# CON_SPDIF_OUT.net
KiCad netlist of a schematic drawn in Altium Designer
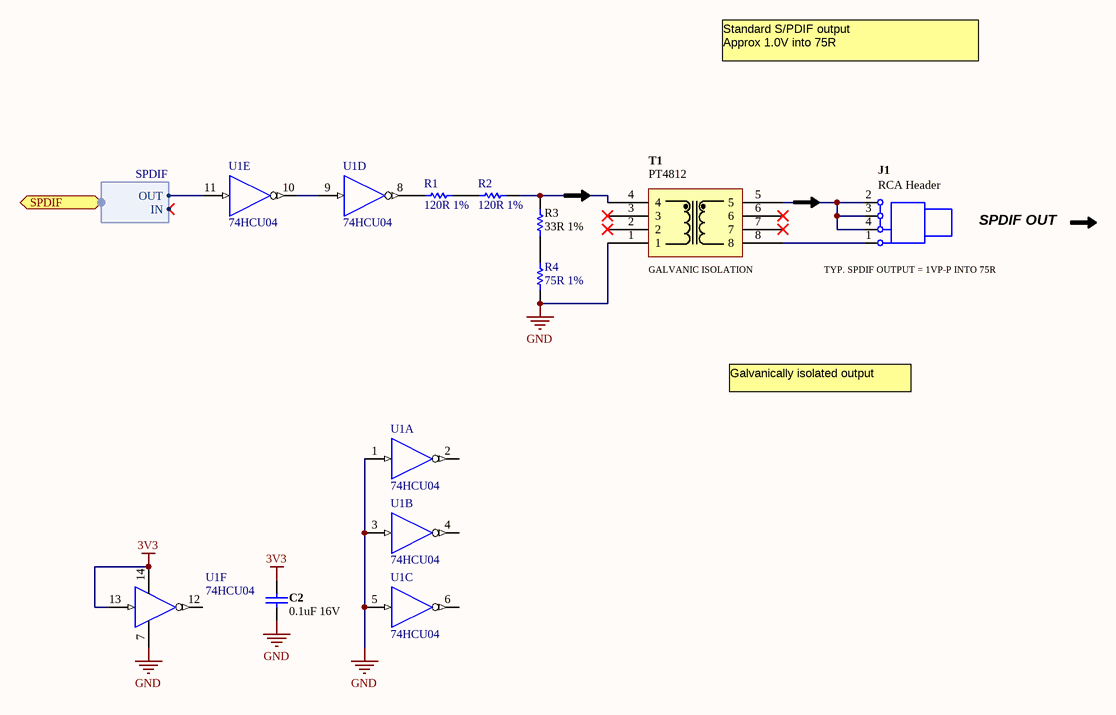
[diagram p0: CON_SPDIF_OUT.SchDoc]

(export (version "E")
  (design (tool "Eeschema 10.0.6"))
  (components
    (comp (ref "C2")
      (value "0.1uF 16V")
      (footprint "CAPC1005-STAR")
      (description "Capacitor, Ceramic, 0.1uF 10% 16V 0402 (1005) X7R")
      (fields (field (name "TOLERANCE") "10 %"))
      (libsource (lib "AltiumDesignLibrary") (part "CAP-NP"))
    )
    (comp (ref "J1")
      (value "RCA Header")
      (footprint "TRC-005")
      (description "Connector, TRC-005-4 , Black RCA Phono Jack, Right Angle, Thru-Hole, Snap-In")
      (libsource (lib "AltiumDesignLibrary") (part "CON-RCA-RA"))
    )
    (comp (ref "R1")
      (value "120R 1%")
      (footprint "RESC1005-STAR")
      (description "Resistor, 120R 1% 0402 (1005)")
      (fields (field (name "TOLERANCE") "1 %"))
      (libsource (lib "AltiumDesignLibrary") (part "RES"))
    )
    (comp (ref "R2")
      (value "120R 1%")
      (footprint "RESC1005-STAR")
      (description "Resistor, 120R 1% 0402 (1005)")
      (fields (field (name "TOLERANCE") "1 %"))
      (libsource (lib "AltiumDesignLibrary") (part "RES"))
    )
    (comp (ref "R3")
      (value "33R 1%")
      (footprint "RESC1005-STAR")
      (description "Resistor, 33R 1% 0402 (1005)")
      (fields (field (name "TOLERANCE") "1 %"))
      (libsource (lib "AltiumDesignLibrary") (part "RES"))
    )
    (comp (ref "R4")
      (value "75R 1%")
      (footprint "RESC1005-STAR")
      (description "Resistor, 75R 1% 0402")
      (fields (field (name "TOLERANCE") "1 %"))
      (libsource (lib "AltiumDesignLibrary") (part "RES"))
    )
    (comp (ref "T1")
      (value "PT4812")
      (footprint "PT4812")
      (description "Transformer, 1:1, SMD, 0 to 70 deg C,  1 to 7 Mbps, 500Vrms min")
      (libsource (lib "AltiumDesignLibrary") (part "PT4812"))
    )
    (comp (ref "U1")
      (value "74HCU04")
      (footprint "SOIC127P600-14")
      (description "74HCU04, HEX Inverter, Unbuffered")
      (libsource (lib "AltiumDesignLibrary") (part "74xx04"))
    )
  )
  (nets
    (net (code "2") (name "/OUT") (class "Default")
      (node (ref "U1") (pin "11") (pinfunction "A_11") (pintype "input"))
    )
    (net (code "4") (name "3V3") (class "Default")
      (node (ref "C2") (pin "2") (pinfunction "2_2") (pintype "passive"))
      (node (ref "U1") (pin "13") (pinfunction "A_13") (pintype "input"))
      (node (ref "U1") (pin "14") (pinfunction "VCC_14") (pintype "power_in"))
    )
    (net (code "5") (name "GND") (class "Default")
      (node (ref "C2") (pin "1") (pinfunction "1_1") (pintype "passive"))
      (node (ref "R4") (pin "2") (pinfunction "2_2") (pintype "passive"))
      (node (ref "T1") (pin "1") (pinfunction "1_1") (pintype "passive"))
      (node (ref "U1") (pin "1") (pinfunction "A_1") (pintype "input"))
      (node (ref "U1") (pin "3") (pinfunction "A_3") (pintype "input"))
      (node (ref "U1") (pin "5") (pinfunction "A_5") (pintype "input"))
      (node (ref "U1") (pin "7") (pinfunction "GND_7") (pintype "power_in"))
    )
    (net (code "6") (name "Net-(J1-Black)") (class "Default")
      (node (ref "J1") (pin "1") (pinfunction "Black_1") (pintype "passive"))
      (node (ref "T1") (pin "8") (pinfunction "8_8") (pintype "passive"))
    )
    (net (code "7") (name "Net-(J1-Red)") (class "Default")
      (node (ref "J1") (pin "2") (pinfunction "Yellow_2") (pintype "passive"))
      (node (ref "J1") (pin "3") (pinfunction "White_3") (pintype "passive"))
      (node (ref "J1") (pin "4") (pinfunction "Red_4") (pintype "passive"))
      (node (ref "T1") (pin "5") (pinfunction "5_5") (pintype "passive"))
    )
    (net (code "8") (name "Net-(R1-Pad2)") (class "Default")
      (node (ref "R1") (pin "2") (pinfunction "2_2") (pintype "passive"))
      (node (ref "R2") (pin "1") (pinfunction "1_1") (pintype "passive"))
    )
    (net (code "9") (name "Net-(R2-Pad2)") (class "Default")
      (node (ref "R2") (pin "2") (pinfunction "2_2") (pintype "passive"))
      (node (ref "R3") (pin "2") (pinfunction "2_2") (pintype "passive"))
      (node (ref "T1") (pin "4") (pinfunction "4_4") (pintype "passive"))
    )
    (net (code "10") (name "Net-(R3-Pad1)") (class "Default")
      (node (ref "R3") (pin "1") (pinfunction "1_1") (pintype "passive"))
      (node (ref "R4") (pin "1") (pinfunction "1_1") (pintype "passive"))
    )
    (net (code "11") (name "Net-(U1D-A)") (class "Default")
      (node (ref "U1") (pin "10") (pinfunction "Y_10") (pintype "output"))
      (node (ref "U1") (pin "9") (pinfunction "A_9") (pintype "input"))
    )
    (net (code "12") (name "Net-(U1D-Y)") (class "Default")
      (node (ref "R1") (pin "1") (pinfunction "1_1") (pintype "passive"))
      (node (ref "U1") (pin "8") (pinfunction "Y_8") (pintype "output"))
    )
    (net (code "13") (name "unconnected-(T1-Pad2)") (class "Default")
      (node (ref "T1") (pin "2") (pinfunction "2_2") (pintype "passive+no_connect"))
    )
    (net (code "14") (name "unconnected-(T1-Pad3)") (class "Default")
      (node (ref "T1") (pin "3") (pinfunction "3_3") (pintype "passive+no_connect"))
    )
    (net (code "15") (name "unconnected-(T1-Pad6)") (class "Default")
      (node (ref "T1") (pin "6") (pinfunction "6_6") (pintype "passive+no_connect"))
    )
    (net (code "16") (name "unconnected-(T1-Pad7)") (class "Default")
      (node (ref "T1") (pin "7") (pinfunction "7_7") (pintype "passive+no_connect"))
    )
    (net (code "17") (name "unconnected-(U1A-Y-Pad2)") (class "Default")
      (node (ref "U1") (pin "2") (pinfunction "Y_2") (pintype "output"))
    )
    (net (code "18") (name "unconnected-(U1B-Y-Pad4)") (class "Default")
      (node (ref "U1") (pin "4") (pinfunction "Y_4") (pintype "output"))
    )
    (net (code "19") (name "unconnected-(U1C-Y-Pad6)") (class "Default")
      (node (ref "U1") (pin "6") (pinfunction "Y_6") (pintype "output"))
    )
    (net (code "20") (name "unconnected-(U1F-Y-Pad12)") (class "Default")
      (node (ref "U1") (pin "12") (pinfunction "Y_12") (pintype "output"))
    )
  )
)
